# Collision_Logic.net
KiCad netlist of a schematic drawn in EAGLE
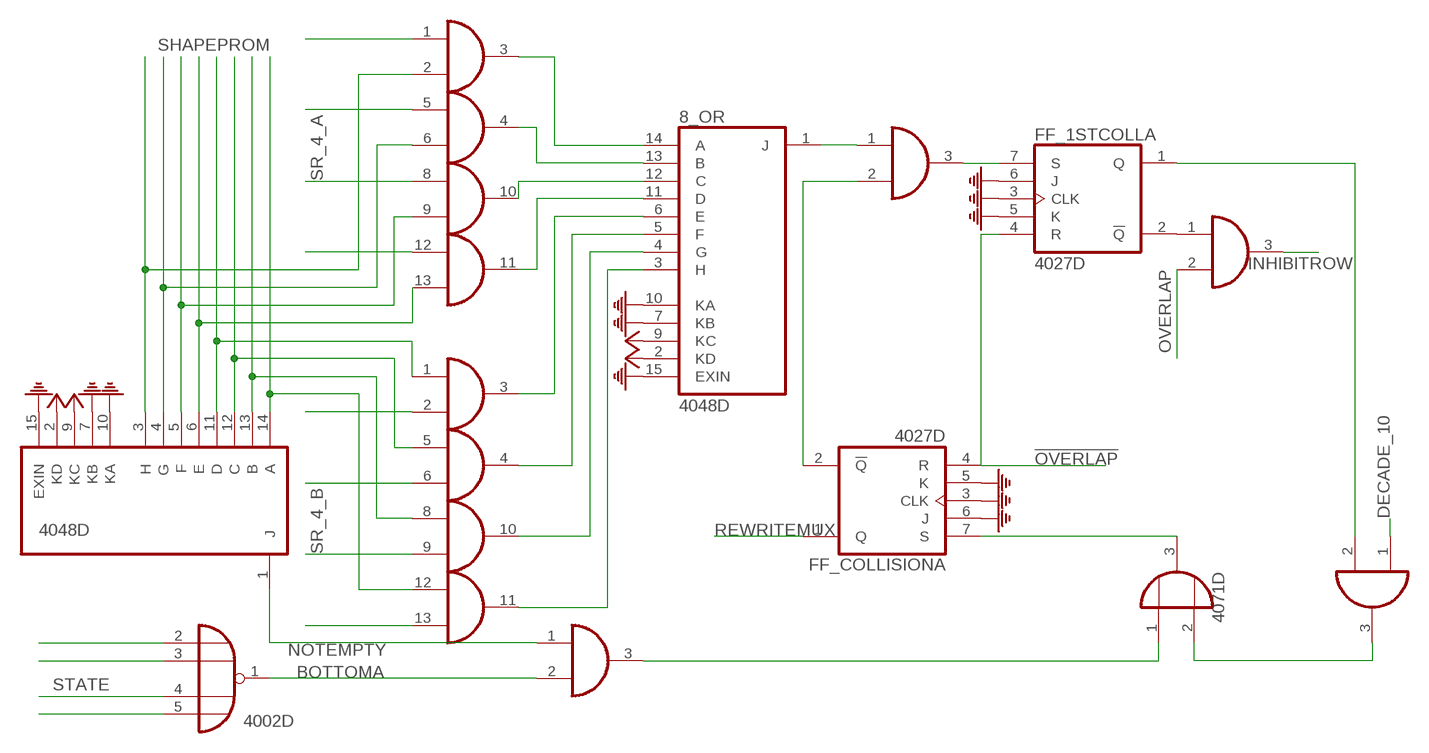
[diagram p0: schematic, sheet 1]

(export (version "E")
  (design (tool "Eeschema 10.0.6"))
  (components
    (comp (ref "8_OR")
      (value "4048D")
      (footprint "eagle-import:SO16")
      (libsource (lib "eagle-import") (part "4048D"))
    )
    (comp (ref "BOTTOM")
      (value "4002D")
      (footprint "eagle-import:SO14")
      (libsource (lib "eagle-import") (part "4002D"))
    )
    (comp (ref "FF_1STCOLL")
      (value "4027D")
      (footprint "eagle-import:SO16")
      (libsource (lib "eagle-import") (part "4027D"))
    )
    (comp (ref "FF_COLLISION")
      (value "4027D")
      (footprint "eagle-import:SO16")
      (libsource (lib "eagle-import") (part "4027D"))
    )
    (comp (ref "IC1")
      (value "4081D")
      (footprint "eagle-import:SO14")
      (libsource (lib "eagle-import") (part "4081D"))
    )
    (comp (ref "IC2")
      (value "4081D")
      (footprint "eagle-import:SO14")
      (libsource (lib "eagle-import") (part "4081D"))
    )
    (comp (ref "IC3")
      (value "4081D")
      (footprint "eagle-import:SO14")
      (libsource (lib "eagle-import") (part "4081D"))
    )
    (comp (ref "IC4")
      (value "4081D")
      (footprint "eagle-import:SO14")
      (libsource (lib "eagle-import") (part "4081D"))
    )
    (comp (ref "IC5")
      (value "4081D")
      (footprint "eagle-import:SO14")
      (libsource (lib "eagle-import") (part "4081D"))
    )
    (comp (ref "IC8")
      (value "4081D")
      (footprint "eagle-import:SO14")
      (libsource (lib "eagle-import") (part "4081D"))
    )
    (comp (ref "IC9")
      (value "4071D")
      (footprint "eagle-import:SO14")
      (libsource (lib "eagle-import") (part "4071D"))
    )
    (comp (ref "NOTEMPTY")
      (value "4048D")
      (footprint "eagle-import:SO16")
      (libsource (lib "eagle-import") (part "4048D"))
    )
  )
  (nets
    (net (code "1") (name "/DECADE_10") (class "Default")
      (node (ref "IC3") (pin "1") (pinfunction "I0_1") (pintype "input"))
    )
    (net (code "2") (name "/INHIBITROW") (class "Default")
      (node (ref "IC5") (pin "3") (pinfunction "O_3") (pintype "output"))
    )
    (net (code "3") (name "/N$5") (class "Default")
      (node (ref "BOTTOM") (pin "2") (pinfunction "I0_2") (pintype "input"))
      (node (ref "BOTTOM") (pin "3") (pinfunction "I1_3") (pintype "input"))
      (node (ref "BOTTOM") (pin "4") (pinfunction "I2_4") (pintype "input"))
    )
    (net (code "4") (name "/OVERLAP") (class "Default")
      (node (ref "IC5") (pin "2") (pinfunction "I1_2") (pintype "input"))
    )
    (net (code "5") (name "/REWRITEMUX") (class "Default")
      (node (ref "FF_COLLISION") (pin "1") (pinfunction "Q_1") (pintype "output"))
    )
    (net (code "6") (name "/SHAPEPROM") (class "Default")
      (node (ref "IC1") (pin "6") (pinfunction "I1_6") (pintype "input"))
      (node (ref "NOTEMPTY") (pin "4") (pinfunction "G_4") (pintype "input"))
    )
    (net (code "7") (name "/SR_4_A") (class "Default")
      (node (ref "IC1") (pin "5") (pinfunction "I0_5") (pintype "input"))
    )
    (net (code "8") (name "/SR_4_B") (class "Default")
      (node (ref "IC2") (pin "6") (pinfunction "I1_6") (pintype "input"))
    )
    (net (code "9") (name "/STATE") (class "Default")
      (node (ref "BOTTOM") (pin "5") (pinfunction "I3_5") (pintype "input"))
    )
    (net (code "10") (name "/~{OVERLAP}") (class "Default")
      (node (ref "FF_1STCOLL") (pin "4") (pinfunction "R_4") (pintype "input"))
      (node (ref "FF_COLLISION") (pin "4") (pinfunction "R_4") (pintype "input"))
    )
    (net (code "11") (name "Net-(8_ORA-A)") (class "Default")
      (node (ref "8_OR") (pin "14") (pinfunction "A_14") (pintype "input"))
      (node (ref "IC1") (pin "3") (pinfunction "O_3") (pintype "output"))
    )
    (net (code "12") (name "Net-(8_ORA-B)") (class "Default")
      (node (ref "8_OR") (pin "13") (pinfunction "B_13") (pintype "input"))
      (node (ref "IC1") (pin "4") (pinfunction "O_4") (pintype "output"))
    )
    (net (code "13") (name "Net-(8_ORA-C)") (class "Default")
      (node (ref "8_OR") (pin "12") (pinfunction "C_12") (pintype "input"))
      (node (ref "IC1") (pin "10") (pinfunction "O_10") (pintype "output"))
    )
    (net (code "14") (name "Net-(8_ORA-D)") (class "Default")
      (node (ref "8_OR") (pin "11") (pinfunction "D_11") (pintype "input"))
      (node (ref "IC1") (pin "11") (pinfunction "O_11") (pintype "output"))
    )
    (net (code "15") (name "Net-(8_ORA-E)") (class "Default")
      (node (ref "8_OR") (pin "6") (pinfunction "E_6") (pintype "input"))
      (node (ref "IC2") (pin "3") (pinfunction "O_3") (pintype "output"))
    )
    (net (code "16") (name "Net-(8_ORA-F)") (class "Default")
      (node (ref "8_OR") (pin "5") (pinfunction "F_5") (pintype "input"))
      (node (ref "IC2") (pin "4") (pinfunction "O_4") (pintype "output"))
    )
    (net (code "17") (name "Net-(8_ORA-G)") (class "Default")
      (node (ref "8_OR") (pin "4") (pinfunction "G_4") (pintype "input"))
      (node (ref "IC2") (pin "10") (pinfunction "O_10") (pintype "output"))
    )
    (net (code "18") (name "Net-(8_ORA-H)") (class "Default")
      (node (ref "8_OR") (pin "3") (pinfunction "H_3") (pintype "input"))
      (node (ref "IC2") (pin "11") (pinfunction "O_11") (pintype "output"))
    )
    (net (code "19") (name "Net-(8_ORA-J)") (class "Default")
      (node (ref "8_OR") (pin "1") (pinfunction "J_1") (pintype "output"))
      (node (ref "IC4") (pin "1") (pinfunction "I0_1") (pintype "input"))
    )
    (net (code "20") (name "Net-(BOTTOMA-O)") (class "Default")
      (node (ref "BOTTOM") (pin "1") (pinfunction "O_1") (pintype "output"))
      (node (ref "IC8") (pin "2") (pinfunction "I1_2") (pintype "input"))
    )
    (net (code "21") (name "Net-(FF_1STCOLLA-Q)") (class "Default")
      (node (ref "FF_1STCOLL") (pin "1") (pinfunction "Q_1") (pintype "output"))
      (node (ref "IC3") (pin "2") (pinfunction "I1_2") (pintype "input"))
    )
    (net (code "22") (name "Net-(FF_1STCOLLA-S)") (class "Default")
      (node (ref "FF_1STCOLL") (pin "7") (pinfunction "S_7") (pintype "input"))
      (node (ref "IC4") (pin "3") (pinfunction "O_3") (pintype "output"))
    )
    (net (code "23") (name "Net-(FF_1STCOLLA-~{Q})") (class "Default")
      (node (ref "FF_1STCOLL") (pin "2") (pinfunction "~{Q}_2") (pintype "output"))
      (node (ref "IC5") (pin "1") (pinfunction "I0_1") (pintype "input"))
    )
    (net (code "24") (name "Net-(FF_COLLISIONA-S)") (class "Default")
      (node (ref "FF_COLLISION") (pin "7") (pinfunction "S_7") (pintype "input"))
      (node (ref "IC9") (pin "3") (pinfunction "O_3") (pintype "output"))
    )
    (net (code "25") (name "Net-(FF_COLLISIONA-~{Q})") (class "Default")
      (node (ref "FF_COLLISION") (pin "2") (pinfunction "~{Q}_2") (pintype "output"))
      (node (ref "IC4") (pin "2") (pinfunction "I1_2") (pintype "input"))
    )
    (net (code "26") (name "Net-(IC1A-I1)") (class "Default")
      (node (ref "IC1") (pin "2") (pinfunction "I1_2") (pintype "input"))
      (node (ref "NOTEMPTY") (pin "3") (pinfunction "H_3") (pintype "input"))
    )
    (net (code "27") (name "Net-(IC1C-I1)") (class "Default")
      (node (ref "IC1") (pin "9") (pinfunction "I1_9") (pintype "input"))
      (node (ref "NOTEMPTY") (pin "5") (pinfunction "F_5") (pintype "input"))
    )
    (net (code "28") (name "Net-(IC1D-I1)") (class "Default")
      (node (ref "IC1") (pin "13") (pinfunction "I1_13") (pintype "input"))
      (node (ref "NOTEMPTY") (pin "6") (pinfunction "E_6") (pintype "input"))
    )
    (net (code "29") (name "Net-(IC2A-I0)") (class "Default")
      (node (ref "IC2") (pin "1") (pinfunction "I0_1") (pintype "input"))
      (node (ref "NOTEMPTY") (pin "11") (pinfunction "D_11") (pintype "input"))
    )
    (net (code "30") (name "Net-(IC2B-I0)") (class "Default")
      (node (ref "IC2") (pin "5") (pinfunction "I0_5") (pintype "input"))
      (node (ref "NOTEMPTY") (pin "12") (pinfunction "C_12") (pintype "input"))
    )
    (net (code "31") (name "Net-(IC2C-I0)") (class "Default")
      (node (ref "IC2") (pin "8") (pinfunction "I0_8") (pintype "input"))
      (node (ref "NOTEMPTY") (pin "13") (pinfunction "B_13") (pintype "input"))
    )
    (net (code "32") (name "Net-(IC2D-I0)") (class "Default")
      (node (ref "IC2") (pin "12") (pinfunction "I0_12") (pintype "input"))
      (node (ref "NOTEMPTY") (pin "14") (pinfunction "A_14") (pintype "input"))
    )
    (net (code "33") (name "Net-(IC3A-O)") (class "Default")
      (node (ref "IC3") (pin "3") (pinfunction "O_3") (pintype "output"))
      (node (ref "IC9") (pin "2") (pinfunction "I1_2") (pintype "input"))
    )
    (net (code "34") (name "Net-(IC8A-I0)") (class "Default")
      (node (ref "IC8") (pin "1") (pinfunction "I0_1") (pintype "input"))
      (node (ref "NOTEMPTY") (pin "1") (pinfunction "J_1") (pintype "output"))
    )
    (net (code "35") (name "Net-(IC8A-O)") (class "Default")
      (node (ref "IC8") (pin "3") (pinfunction "O_3") (pintype "output"))
      (node (ref "IC9") (pin "1") (pinfunction "I0_1") (pintype "input"))
    )
    (net (code "36") (name "PE") (class "Default")
      (node (ref "8_OR") (pin "10") (pinfunction "KA_10") (pintype "input"))
      (node (ref "8_OR") (pin "15") (pinfunction "EXIN_15") (pintype "input"))
      (node (ref "8_OR") (pin "7") (pinfunction "KB_7") (pintype "input"))
      (node (ref "FF_1STCOLL") (pin "3") (pinfunction "CLK_3") (pintype "input"))
      (node (ref "FF_1STCOLL") (pin "5") (pinfunction "K_5") (pintype "input"))
      (node (ref "FF_1STCOLL") (pin "6") (pinfunction "J_6") (pintype "input"))
      (node (ref "FF_COLLISION") (pin "3") (pinfunction "CLK_3") (pintype "input"))
      (node (ref "FF_COLLISION") (pin "5") (pinfunction "K_5") (pintype "input"))
      (node (ref "FF_COLLISION") (pin "6") (pinfunction "J_6") (pintype "input"))
      (node (ref "NOTEMPTY") (pin "10") (pinfunction "KA_10") (pintype "input"))
      (node (ref "NOTEMPTY") (pin "15") (pinfunction "EXIN_15") (pintype "input"))
      (node (ref "NOTEMPTY") (pin "7") (pinfunction "KB_7") (pintype "input"))
    )
    (net (code "37") (name "V+") (class "Default")
      (node (ref "8_OR") (pin "2") (pinfunction "KD_2") (pintype "input"))
      (node (ref "8_OR") (pin "9") (pinfunction "KC_9") (pintype "input"))
      (node (ref "NOTEMPTY") (pin "2") (pinfunction "KD_2") (pintype "input"))
      (node (ref "NOTEMPTY") (pin "9") (pinfunction "KC_9") (pintype "input"))
    )
    (net (code "38") (name "unconnected-(IC1A-I0-Pad1)") (class "Default")
      (node (ref "IC1") (pin "1") (pinfunction "I0_1") (pintype "input"))
    )
    (net (code "39") (name "unconnected-(IC1C-I0-Pad8)") (class "Default")
      (node (ref "IC1") (pin "8") (pinfunction "I0_8") (pintype "input"))
    )
    (net (code "40") (name "unconnected-(IC1D-I0-Pad12)") (class "Default")
      (node (ref "IC1") (pin "12") (pinfunction "I0_12") (pintype "input"))
    )
    (net (code "41") (name "unconnected-(IC2A-I1-Pad2)") (class "Default")
      (node (ref "IC2") (pin "2") (pinfunction "I1_2") (pintype "input"))
    )
    (net (code "42") (name "unconnected-(IC2C-I1-Pad9)") (class "Default")
      (node (ref "IC2") (pin "9") (pinfunction "I1_9") (pintype "input"))
    )
    (net (code "43") (name "unconnected-(IC2D-I1-Pad13)") (class "Default")
      (node (ref "IC2") (pin "13") (pinfunction "I1_13") (pintype "input"))
    )
  )
)
